# rapidshark-lipo-sensor-mk-2_2.net
KiCad netlist of a schematic drawn in EAGLE
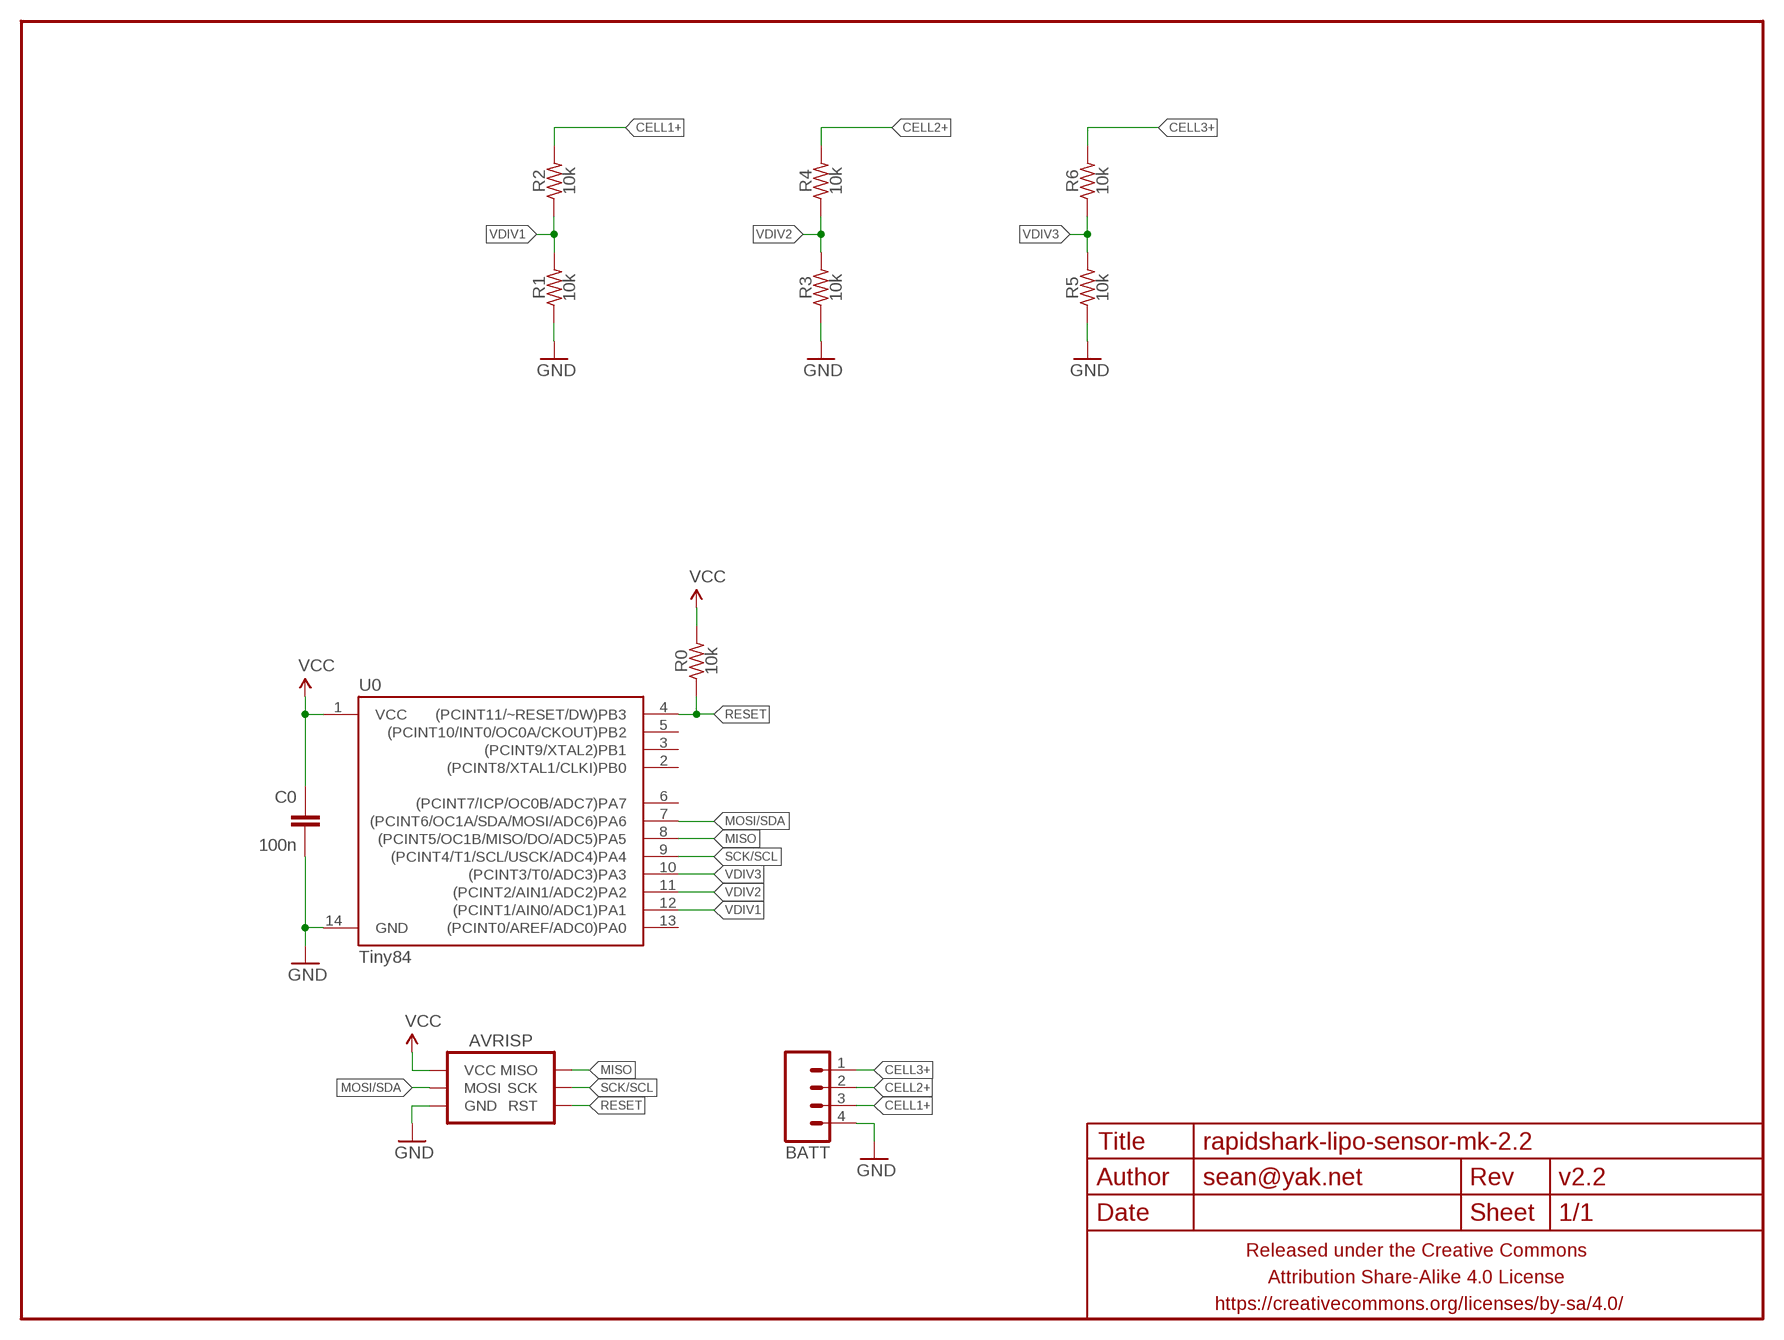
[diagram p0: schematic, sheet 1]

(export (version "E")
  (design (tool "Eeschema 10.0.6"))
  (components
    (comp (ref "AVRISP")
      (value "AVR_SPI_PRG_6PTH_INLINE_I2C")
      (footprint "eagle-import:AVR_ISP_INLINE_PTH_I2C")
      (libsource (lib "eagle-import") (part "AVR_SPI_PRG_6PTH_INLINE_I2C"))
    )
    (comp (ref "BATT")
      (value "M04JST_XH_VERT")
      (footprint "eagle-import:JST-4-XH-VERT-TH")
      (libsource (lib "eagle-import") (part "M04JST_XH_VERT"))
    )
    (comp (ref "C0")
      (value "100n")
      (footprint "eagle-import:C025-024X044")
      (libsource (lib "eagle-import") (part "CAPACITOR-CERAMIC025-024X044"))
    )
    (comp (ref "FRAME1")
      (value "FRAME-LETTERNO_PACKAGE")
      (footprint "eagle-import:DUMMY")
      (fields (field (name "DESIGNER") "sean@yak.net") (field (name "VERSION") "v2.2"))
      (libsource (lib "eagle-import") (part "FRAME-LETTERNO_PACKAGE"))
    )
    (comp (ref "R0")
      (value "10k")
      (footprint "eagle-import:RESISTOR-AXIAL-PTH-5.08MM")
      (libsource (lib "eagle-import") (part "RESISTORPTH-AXIAL-5.08MM"))
    )
    (comp (ref "R1")
      (value "10k")
      (footprint "eagle-import:RESISTOR-AXIAL-PTH-5.08MM")
      (libsource (lib "eagle-import") (part "RESISTORPTH-AXIAL-5.08MM"))
    )
    (comp (ref "R2")
      (value "10k")
      (footprint "eagle-import:RESISTOR-AXIAL-PTH-5.08MM")
      (libsource (lib "eagle-import") (part "RESISTORPTH-AXIAL-5.08MM"))
    )
    (comp (ref "R3")
      (value "10k")
      (footprint "eagle-import:RESISTOR-AXIAL-PTH-5.08MM")
      (libsource (lib "eagle-import") (part "RESISTORPTH-AXIAL-5.08MM"))
    )
    (comp (ref "R4")
      (value "10k")
      (footprint "eagle-import:RESISTOR-AXIAL-PTH-5.08MM")
      (libsource (lib "eagle-import") (part "RESISTORPTH-AXIAL-5.08MM"))
    )
    (comp (ref "R5")
      (value "10k")
      (footprint "eagle-import:RESISTOR-AXIAL-PTH-5.08MM")
      (libsource (lib "eagle-import") (part "RESISTORPTH-AXIAL-5.08MM"))
    )
    (comp (ref "R6")
      (value "10k")
      (footprint "eagle-import:RESISTOR-AXIAL-PTH-5.08MM")
      (libsource (lib "eagle-import") (part "RESISTORPTH-AXIAL-5.08MM"))
    )
    (comp (ref "U0")
      (value "Tiny84")
      (footprint "eagle-import:DIL14")
      (libsource (lib "eagle-import") (part "ATTINY84ATTINY84-20PU"))
    )
  )
  (nets
    (net (code "1") (name "CELL1+") (class "Default")
      (node (ref "BATT") (pin "3") (pinfunction "3_3") (pintype "passive"))
      (node (ref "R2") (pin "P$2") (pinfunction "2_P$2") (pintype "passive"))
    )
    (net (code "2") (name "CELL2+") (class "Default")
      (node (ref "BATT") (pin "2") (pinfunction "2_2") (pintype "passive"))
      (node (ref "R4") (pin "P$2") (pinfunction "2_P$2") (pintype "passive"))
    )
    (net (code "3") (name "CELL3+") (class "Default")
      (node (ref "BATT") (pin "1") (pinfunction "1_1") (pintype "passive"))
      (node (ref "R6") (pin "P$2") (pinfunction "2_P$2") (pintype "passive"))
    )
    (net (code "4") (name "GND") (class "Default")
      (node (ref "AVRISP") (pin "GND") (pinfunction "GND_GND") (pintype "passive"))
      (node (ref "BATT") (pin "4") (pinfunction "4_4") (pintype "passive"))
      (node (ref "C0") (pin "2") (pinfunction "2_2") (pintype "passive"))
      (node (ref "R1") (pin "P$1") (pinfunction "1_P$1") (pintype "passive"))
      (node (ref "R3") (pin "P$1") (pinfunction "1_P$1") (pintype "passive"))
      (node (ref "R5") (pin "P$1") (pinfunction "1_P$1") (pintype "passive"))
      (node (ref "U0") (pin "14") (pinfunction "GND_14") (pintype "bidirectional"))
    )
    (net (code "5") (name "MISO") (class "Default")
      (node (ref "AVRISP") (pin "MISO") (pinfunction "MISO_MISO") (pintype "passive"))
      (node (ref "U0") (pin "8") (pinfunction "(PCINT5/OC1B/MISO/DO/ADC5)PA5_8") (pintype "bidirectional"))
    )
    (net (code "6") (name "MOSI{slash}SDA") (class "Default")
      (node (ref "AVRISP") (pin "MOSI") (pinfunction "MOSI_MOSI") (pintype "passive"))
      (node (ref "U0") (pin "7") (pinfunction "(PCINT6/OC1A/SDA/MOSI/ADC6)PA6_7") (pintype "bidirectional"))
    )
    (net (code "7") (name "RESET") (class "Default")
      (node (ref "AVRISP") (pin "RESET") (pinfunction "RST_RESET") (pintype "passive"))
      (node (ref "R0") (pin "P$1") (pinfunction "1_P$1") (pintype "passive"))
      (node (ref "U0") (pin "4") (pinfunction "(PCINT11/~{RESET/DW})PB3_4") (pintype "bidirectional"))
    )
    (net (code "8") (name "SCK{slash}SCL") (class "Default")
      (node (ref "AVRISP") (pin "SCK") (pinfunction "SCK_SCK") (pintype "passive"))
      (node (ref "U0") (pin "9") (pinfunction "(PCINT4/T1/SCL/USCK/ADC4)PA4_9") (pintype "bidirectional"))
    )
    (net (code "9") (name "VCC") (class "Default")
      (node (ref "AVRISP") (pin "VCC") (pinfunction "VCC_VCC") (pintype "passive"))
      (node (ref "C0") (pin "1") (pinfunction "1_1") (pintype "passive"))
      (node (ref "R0") (pin "P$2") (pinfunction "2_P$2") (pintype "passive"))
      (node (ref "U0") (pin "1") (pinfunction "VCC_1") (pintype "bidirectional"))
    )
    (net (code "10") (name "VDIV1") (class "Default")
      (node (ref "R1") (pin "P$2") (pinfunction "2_P$2") (pintype "passive"))
      (node (ref "R2") (pin "P$1") (pinfunction "1_P$1") (pintype "passive"))
      (node (ref "U0") (pin "12") (pinfunction "(PCINT1/AIN0/ADC1)PA1_12") (pintype "bidirectional"))
    )
    (net (code "11") (name "VDIV2") (class "Default")
      (node (ref "R3") (pin "P$2") (pinfunction "2_P$2") (pintype "passive"))
      (node (ref "R4") (pin "P$1") (pinfunction "1_P$1") (pintype "passive"))
      (node (ref "U0") (pin "11") (pinfunction "(PCINT2/AIN1/ADC2)PA2_11") (pintype "bidirectional"))
    )
    (net (code "12") (name "VDIV3") (class "Default")
      (node (ref "R5") (pin "P$2") (pinfunction "2_P$2") (pintype "passive"))
      (node (ref "R6") (pin "P$1") (pinfunction "1_P$1") (pintype "passive"))
      (node (ref "U0") (pin "10") (pinfunction "(PCINT3/T0/ADC3)PA3_10") (pintype "bidirectional"))
    )
    (net (code "13") (name "unconnected-(U0-(PCINT0{slash}AREF{slash}ADC0)PA0-Pad13)") (class "Default")
      (node (ref "U0") (pin "13") (pinfunction "(PCINT0/AREF/ADC0)PA0_13") (pintype "bidirectional"))
    )
    (net (code "14") (name "unconnected-(U0-(PCINT7{slash}ICP{slash}OC0B{slash}ADC7)PA7-Pad6)") (class "Default")
      (node (ref "U0") (pin "6") (pinfunction "(PCINT7/ICP/OC0B/ADC7)PA7_6") (pintype "bidirectional"))
    )
    (net (code "15") (name "unconnected-(U0-(PCINT8{slash}XTAL1{slash}CLKI)PB0-Pad2)") (class "Default")
      (node (ref "U0") (pin "2") (pinfunction "(PCINT8/XTAL1/CLKI)PB0_2") (pintype "bidirectional"))
    )
    (net (code "16") (name "unconnected-(U0-(PCINT9{slash}XTAL2)PB1-Pad3)") (class "Default")
      (node (ref "U0") (pin "3") (pinfunction "(PCINT9/XTAL2)PB1_3") (pintype "bidirectional"))
    )
    (net (code "17") (name "unconnected-(U0-(PCINT10{slash}INT0{slash}OC0A{slash}CKOUT)PB2-Pad5)") (class "Default")
      (node (ref "U0") (pin "5") (pinfunction "(PCINT10/INT0/OC0A/CKOUT)PB2_5") (pintype "bidirectional"))
    )
  )
)
